# driver.net
KiCad netlist of a schematic drawn in EAGLE
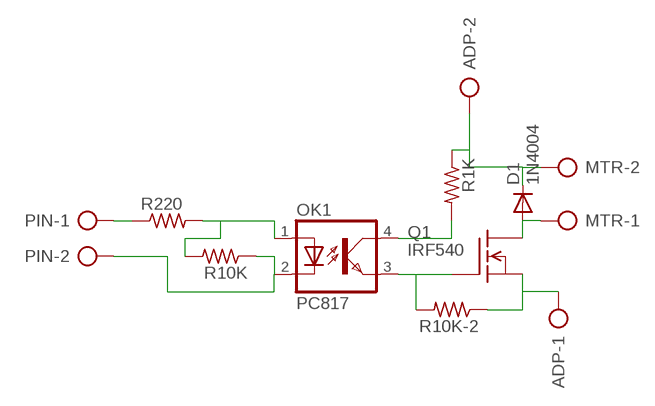
[diagram p0: schematic, sheet 1]

(export (version "E")
  (design (tool "Eeschema 10.0.6"))
  (components
    (comp (ref "ADP")
      (value "AK300/2")
      (footprint "eagle-import:AK300_2")
      (libsource (lib "eagle-import") (part "AK300/2"))
    )
    (comp (ref "D1")
      (value "1N4004")
      (footprint "eagle-import:DO41-10")
      (libsource (lib "eagle-import") (part "1N4004"))
    )
    (comp (ref "MTR")
      (value "AK300/2")
      (footprint "eagle-import:AK300_2")
      (libsource (lib "eagle-import") (part "AK300/2"))
    )
    (comp (ref "OK1")
      (value "PC817")
      (footprint "eagle-import:DIL04")
      (fields (field (name "MPN") "PC817X4J000F"))
      (libsource (lib "eagle-import") (part "PC817"))
    )
    (comp (ref "PIN")
      (value "AK300/2")
      (footprint "eagle-import:AK300_2")
      (libsource (lib "eagle-import") (part "AK300/2"))
    )
    (comp (ref "Q1")
      (value "IRF540")
      (footprint "eagle-import:TO220")
      (libsource (lib "eagle-import") (part "IRF540"))
    )
    (comp (ref "R1K")
      (value "R-US_0204/7")
      (footprint "eagle-import:0204_7")
      (libsource (lib "eagle-import") (part "R-US_0204/7"))
    )
    (comp (ref "R10K")
      (value "R-US_0204/7")
      (footprint "eagle-import:0204_7")
      (libsource (lib "eagle-import") (part "R-US_0204/7"))
    )
    (comp (ref "R10K-2")
      (value "R-US_0204/7")
      (footprint "eagle-import:0204_7")
      (libsource (lib "eagle-import") (part "R-US_0204/7"))
    )
    (comp (ref "R220")
      (value "R-US_0204/7")
      (footprint "eagle-import:0204_7")
      (libsource (lib "eagle-import") (part "R-US_0204/7"))
    )
  )
  (nets
    (net (code "1") (name "Net-(ADPA-KL)") (class "Default")
      (node (ref "ADP") (pin "1") (pinfunction "KL_1") (pintype "passive"))
      (node (ref "Q1") (pin "3") (pinfunction "S_3") (pintype "passive"))
      (node (ref "R10K-2") (pin "1") (pinfunction "1_1") (pintype "passive"))
    )
    (net (code "2") (name "Net-(ADPB-KL)") (class "Default")
      (node (ref "ADP") (pin "2") (pinfunction "KL_2") (pintype "passive"))
      (node (ref "D1") (pin "C") (pinfunction "C_C") (pintype "passive"))
      (node (ref "MTR") (pin "2") (pinfunction "KL_2") (pintype "passive"))
      (node (ref "R1K") (pin "1") (pinfunction "1_1") (pintype "passive"))
    )
    (net (code "3") (name "Net-(MTRA-KL)") (class "Default")
      (node (ref "D1") (pin "A") (pinfunction "A_A") (pintype "passive"))
      (node (ref "MTR") (pin "1") (pinfunction "KL_1") (pintype "passive"))
      (node (ref "Q1") (pin "2") (pinfunction "D_2") (pintype "passive"))
    )
    (net (code "4") (name "Net-(OK1-A)") (class "Default")
      (node (ref "OK1") (pin "1") (pinfunction "A_1") (pintype "passive"))
      (node (ref "R10K") (pin "2") (pinfunction "2_2") (pintype "passive"))
      (node (ref "R220") (pin "2") (pinfunction "2_2") (pintype "passive"))
    )
    (net (code "5") (name "Net-(OK1-C)") (class "Default")
      (node (ref "OK1") (pin "2") (pinfunction "C_2") (pintype "passive"))
      (node (ref "PIN") (pin "2") (pinfunction "KL_2") (pintype "passive"))
      (node (ref "R10K") (pin "1") (pinfunction "1_1") (pintype "passive"))
    )
    (net (code "6") (name "Net-(OK1-COL)") (class "Default")
      (node (ref "OK1") (pin "4") (pinfunction "COL_4") (pintype "passive"))
      (node (ref "R1K") (pin "2") (pinfunction "2_2") (pintype "passive"))
    )
    (net (code "7") (name "Net-(OK1-EMIT)") (class "Default")
      (node (ref "OK1") (pin "3") (pinfunction "EMIT_3") (pintype "passive"))
      (node (ref "Q1") (pin "1") (pinfunction "G_1") (pintype "passive"))
      (node (ref "R10K-2") (pin "2") (pinfunction "2_2") (pintype "passive"))
    )
    (net (code "8") (name "Net-(PINA-KL)") (class "Default")
      (node (ref "PIN") (pin "1") (pinfunction "KL_1") (pintype "passive"))
      (node (ref "R220") (pin "1") (pinfunction "1_1") (pintype "passive"))
    )
  )
)
